# 06-HDMI_KEY_MARK.net
KiCad netlist of a schematic drawn in Altium Designer
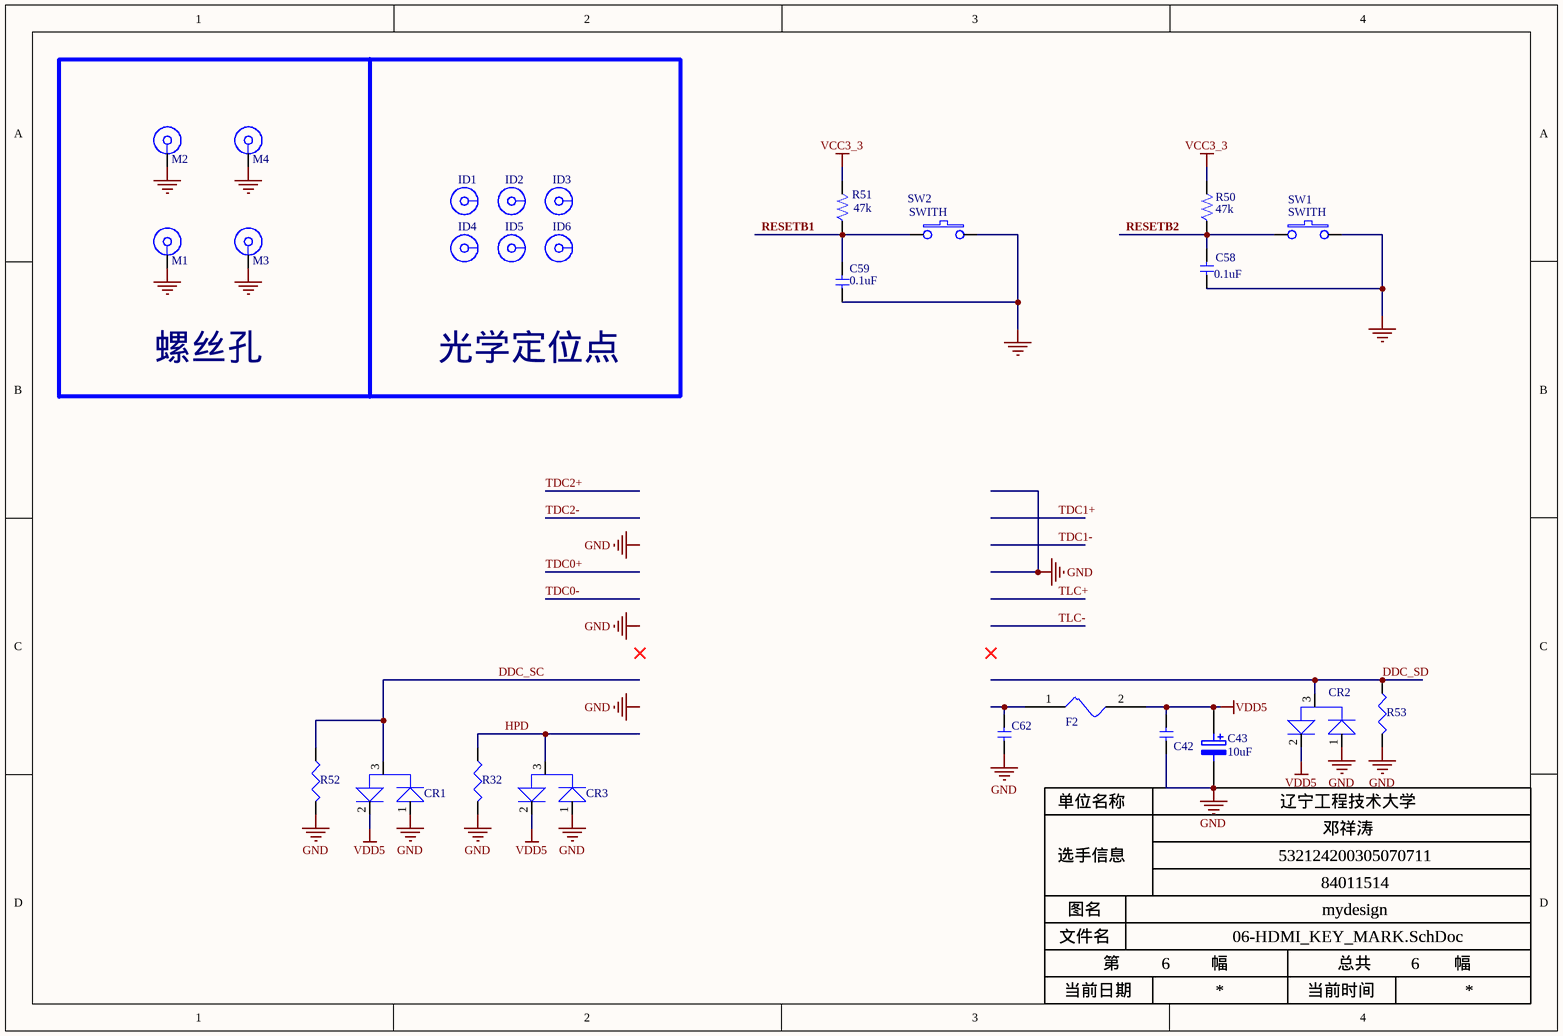
[diagram p0: 06-HDMI_KEY_MARK.SchDoc]

(export (version "E")
  (design (tool "Eeschema 10.0.6"))
  (components
    (comp (ref "C42")
      (value "C_2")
      (footprint "C0603")
      (fields (field (name "VOLTAGE") "CMAX"))
      (libsource (lib "sucaiku") (part "C_2"))
    )
    (comp (ref "C43")
      (value "10uF")
      (footprint "3528-C")
      (description "Electrolytic Capacitor")
      (libsource (lib "sucaiku") (part "ELECTRO2"))
    )
    (comp (ref "C58")
      (value "0.1uF")
      (footprint "C0603")
      (fields (field (name "VOLTAGE") "CMAX") (field (name "Comment") "C_2"))
      (libsource (lib "VIDEO_Demo_Kit_1") (part "C_2"))
    )
    (comp (ref "C59")
      (value "0.1uF")
      (footprint "C0603")
      (fields (field (name "VOLTAGE") "CMAX") (field (name "Comment") "C_2"))
      (libsource (lib "VIDEO_Demo_Kit_1") (part "C_2"))
    )
    (comp (ref "C62")
      (value "C_2")
      (footprint "C0603")
      (fields (field (name "VOLTAGE") "CMAX"))
      (libsource (lib "sucaiku") (part "C_2"))
    )
    (comp (ref "CR1")
      (value "DUALDIODE_1")
      (footprint "SOT-23")
      (libsource (lib "sucaiku") (part "DUALDIODE_1"))
    )
    (comp (ref "CR2")
      (value "DUALDIODE_1")
      (footprint "SOT-23")
      (libsource (lib "sucaiku") (part "DUALDIODE_1"))
    )
    (comp (ref "CR3")
      (value "DUALDIODE_1")
      (footprint "SOT-23")
      (libsource (lib "sucaiku") (part "DUALDIODE_1"))
    )
    (comp (ref "F2") (value "FUSE") (footprint "1206-F") (libsource (lib "sucaiku") (part "FUSE")))
    (comp (ref "ID1")
      (value "HO")
      (footprint "MARKS")
      (fields (field (name "SOURCE_PATH") "C:\\PROGRAM FILES\\印院出品\\CAPTURE 16.2\\LIBRARY\\CONNECTOR.OLB"))
      (libsource (lib "VIDEO_Demo_Kit_1") (part "BNC"))
    )
    (comp (ref "ID2")
      (value "HO")
      (footprint "MARKS")
      (fields (field (name "SOURCE_PATH") "C:\\PROGRAM FILES\\印院出品\\CAPTURE 16.2\\LIBRARY\\CONNECTOR.OLB"))
      (libsource (lib "VIDEO_Demo_Kit_1") (part "BNC"))
    )
    (comp (ref "ID3")
      (value "HO")
      (footprint "MARKS")
      (fields (field (name "SOURCE_PATH") "C:\\PROGRAM FILES\\印院出品\\CAPTURE 16.2\\LIBRARY\\CONNECTOR.OLB"))
      (libsource (lib "VIDEO_Demo_Kit_1") (part "BNC"))
    )
    (comp (ref "ID4")
      (value "HO")
      (footprint "MARKS")
      (fields (field (name "SOURCE_PATH") "C:\\PROGRAM FILES\\印院出品\\CAPTURE 16.2\\LIBRARY\\CONNECTOR.OLB"))
      (libsource (lib "VIDEO_Demo_Kit_1") (part "BNC"))
    )
    (comp (ref "ID5")
      (value "HO")
      (footprint "MARKS")
      (fields (field (name "SOURCE_PATH") "C:\\PROGRAM FILES\\印院出品\\CAPTURE 16.2\\LIBRARY\\CONNECTOR.OLB"))
      (libsource (lib "VIDEO_Demo_Kit_1") (part "BNC"))
    )
    (comp (ref "ID6")
      (value "HO")
      (footprint "MARKS")
      (fields (field (name "SOURCE_PATH") "C:\\PROGRAM FILES\\印院出品\\CAPTURE 16.2\\LIBRARY\\CONNECTOR.OLB"))
      (libsource (lib "VIDEO_Demo_Kit_1") (part "BNC"))
    )
    (comp (ref "M1")
      (value "HO")
      (footprint "MOUNT")
      (fields (field (name "SOURCE_PATH") "C:\\PROGRAM FILES\\印院出品\\CAPTURE 16.2\\LIBRARY\\CONNECTOR.OLB"))
      (libsource (lib "") (part "BNC_1"))
    )
    (comp (ref "M2")
      (value "HO")
      (footprint "MOUNT")
      (fields (field (name "SOURCE_PATH") "C:\\PROGRAM FILES\\印院出品\\CAPTURE 16.2\\LIBRARY\\CONNECTOR.OLB"))
      (libsource (lib "") (part "BNC_1"))
    )
    (comp (ref "M3")
      (value "HO")
      (footprint "MOUNT")
      (fields (field (name "SOURCE_PATH") "C:\\PROGRAM FILES\\印院出品\\CAPTURE 16.2\\LIBRARY\\CONNECTOR.OLB"))
      (libsource (lib "") (part "BNC_1"))
    )
    (comp (ref "M4")
      (value "HO")
      (footprint "MOUNT")
      (fields (field (name "SOURCE_PATH") "C:\\PROGRAM FILES\\印院出品\\CAPTURE 16.2\\LIBRARY\\CONNECTOR.OLB"))
      (libsource (lib "") (part "BNC_1"))
    )
    (comp (ref "R32") (value "R") (footprint "R0603") (libsource (lib "sucaiku") (part "R")))
    (comp (ref "R50")
      (value "47k")
      (footprint "R0603")
      (fields (field (name "POWER") "RMAX") (field (name "VOLTAGE") "RVMAX") (field (name "Comment") "R_3"))
      (libsource (lib "VIDEO_Demo_Kit_1") (part "R_3"))
    )
    (comp (ref "R51")
      (value "47k")
      (footprint "R0603")
      (fields (field (name "POWER") "RMAX") (field (name "VOLTAGE") "RVMAX") (field (name "Comment") "R_3"))
      (libsource (lib "VIDEO_Demo_Kit_1") (part "R_3"))
    )
    (comp (ref "R52") (value "R") (footprint "R0603") (libsource (lib "sucaiku") (part "R")))
    (comp (ref "R53") (value "R") (footprint "R0603") (libsource (lib "sucaiku") (part "R")))
    (comp (ref "SW1")
      (value "SWITH")
      (footprint "SW-280")
      (fields (field (name "Comment") "SW_PUSHBUTTON_2"))
      (libsource (lib "VIDEO_Demo_Kit_1") (part "SW_PUSHBUTTON_2"))
    )
    (comp (ref "SW2")
      (value "SWITH")
      (footprint "SW-280")
      (fields (field (name "Comment") "SW_PUSHBUTTON_2"))
      (libsource (lib "VIDEO_Demo_Kit_1") (part "SW_PUSHBUTTON_2"))
    )
  )
  (nets
    (net (code "1") (name "/DDC_SC") (class "Default")
      (node (ref "CR1") (pin "3") (pinfunction "3_3") (pintype "passive"))
      (node (ref "R52") (pin "1") (pinfunction "1_1") (pintype "passive"))
    )
    (net (code "2") (name "/DDC_SD") (class "Default")
      (node (ref "CR2") (pin "3") (pinfunction "3_3") (pintype "passive"))
      (node (ref "R53") (pin "1") (pinfunction "1_1") (pintype "passive"))
    )
    (net (code "3") (name "/HPD") (class "Default")
      (node (ref "CR3") (pin "3") (pinfunction "3_3") (pintype "passive"))
      (node (ref "R32") (pin "1") (pinfunction "1_1") (pintype "passive"))
    )
    (net (code "4") (name "/RESETB1") (class "Default")
      (node (ref "C59") (pin "2") (pinfunction "2_2") (pintype "passive"))
      (node (ref "R51") (pin "1") (pinfunction "1_1") (pintype "passive"))
      (node (ref "SW2") (pin "1") (pinfunction "1_1") (pintype "passive"))
    )
    (net (code "5") (name "/RESETB2") (class "Default")
      (node (ref "C58") (pin "2") (pinfunction "2_2") (pintype "passive"))
      (node (ref "R50") (pin "1") (pinfunction "1_1") (pintype "passive"))
      (node (ref "SW1") (pin "1") (pinfunction "1_1") (pintype "passive"))
    )
    (net (code "14") (name "GND") (class "Default")
      (node (ref "C42") (pin "1") (pinfunction "1_1") (pintype "passive"))
      (node (ref "C43") (pin "2") (pinfunction "2_2") (pintype "passive"))
      (node (ref "C58") (pin "1") (pinfunction "1_1") (pintype "passive"))
      (node (ref "C59") (pin "1") (pinfunction "1_1") (pintype "passive"))
      (node (ref "C62") (pin "1") (pinfunction "1_1") (pintype "passive"))
      (node (ref "CR1") (pin "1") (pinfunction "1_1") (pintype "passive"))
      (node (ref "CR2") (pin "1") (pinfunction "1_1") (pintype "passive"))
      (node (ref "CR3") (pin "1") (pinfunction "1_1") (pintype "passive"))
      (node (ref "M1") (pin "1") (pinfunction "1_1") (pintype "passive"))
      (node (ref "M2") (pin "1") (pinfunction "1_1") (pintype "passive"))
      (node (ref "M3") (pin "1") (pinfunction "1_1") (pintype "passive"))
      (node (ref "M4") (pin "1") (pinfunction "1_1") (pintype "passive"))
      (node (ref "R32") (pin "2") (pinfunction "2_2") (pintype "passive"))
      (node (ref "R52") (pin "2") (pinfunction "2_2") (pintype "passive"))
      (node (ref "R53") (pin "2") (pinfunction "2_2") (pintype "passive"))
      (node (ref "SW1") (pin "2") (pinfunction "2_2") (pintype "passive"))
      (node (ref "SW2") (pin "2") (pinfunction "2_2") (pintype "passive"))
    )
    (net (code "15") (name "Net-(C62-Pad2)") (class "Default")
      (node (ref "C62") (pin "2") (pinfunction "2_2") (pintype "passive"))
      (node (ref "F2") (pin "1") (pinfunction "1_1") (pintype "passive"))
    )
    (net (code "16") (name "VCC3_3") (class "Default")
      (node (ref "R50") (pin "2") (pinfunction "2_2") (pintype "passive"))
      (node (ref "R51") (pin "2") (pinfunction "2_2") (pintype "passive"))
    )
    (net (code "17") (name "VDD5") (class "Default")
      (node (ref "C42") (pin "2") (pinfunction "2_2") (pintype "passive"))
      (node (ref "C43") (pin "1") (pinfunction "1_1") (pintype "passive"))
      (node (ref "CR1") (pin "2") (pinfunction "2_2") (pintype "passive"))
      (node (ref "CR2") (pin "2") (pinfunction "2_2") (pintype "passive"))
      (node (ref "CR3") (pin "2") (pinfunction "2_2") (pintype "passive"))
      (node (ref "F2") (pin "2") (pinfunction "2_2") (pintype "passive"))
    )
  )
)
